# design.net
KiCad netlist of a schematic drawn in EasyEDA
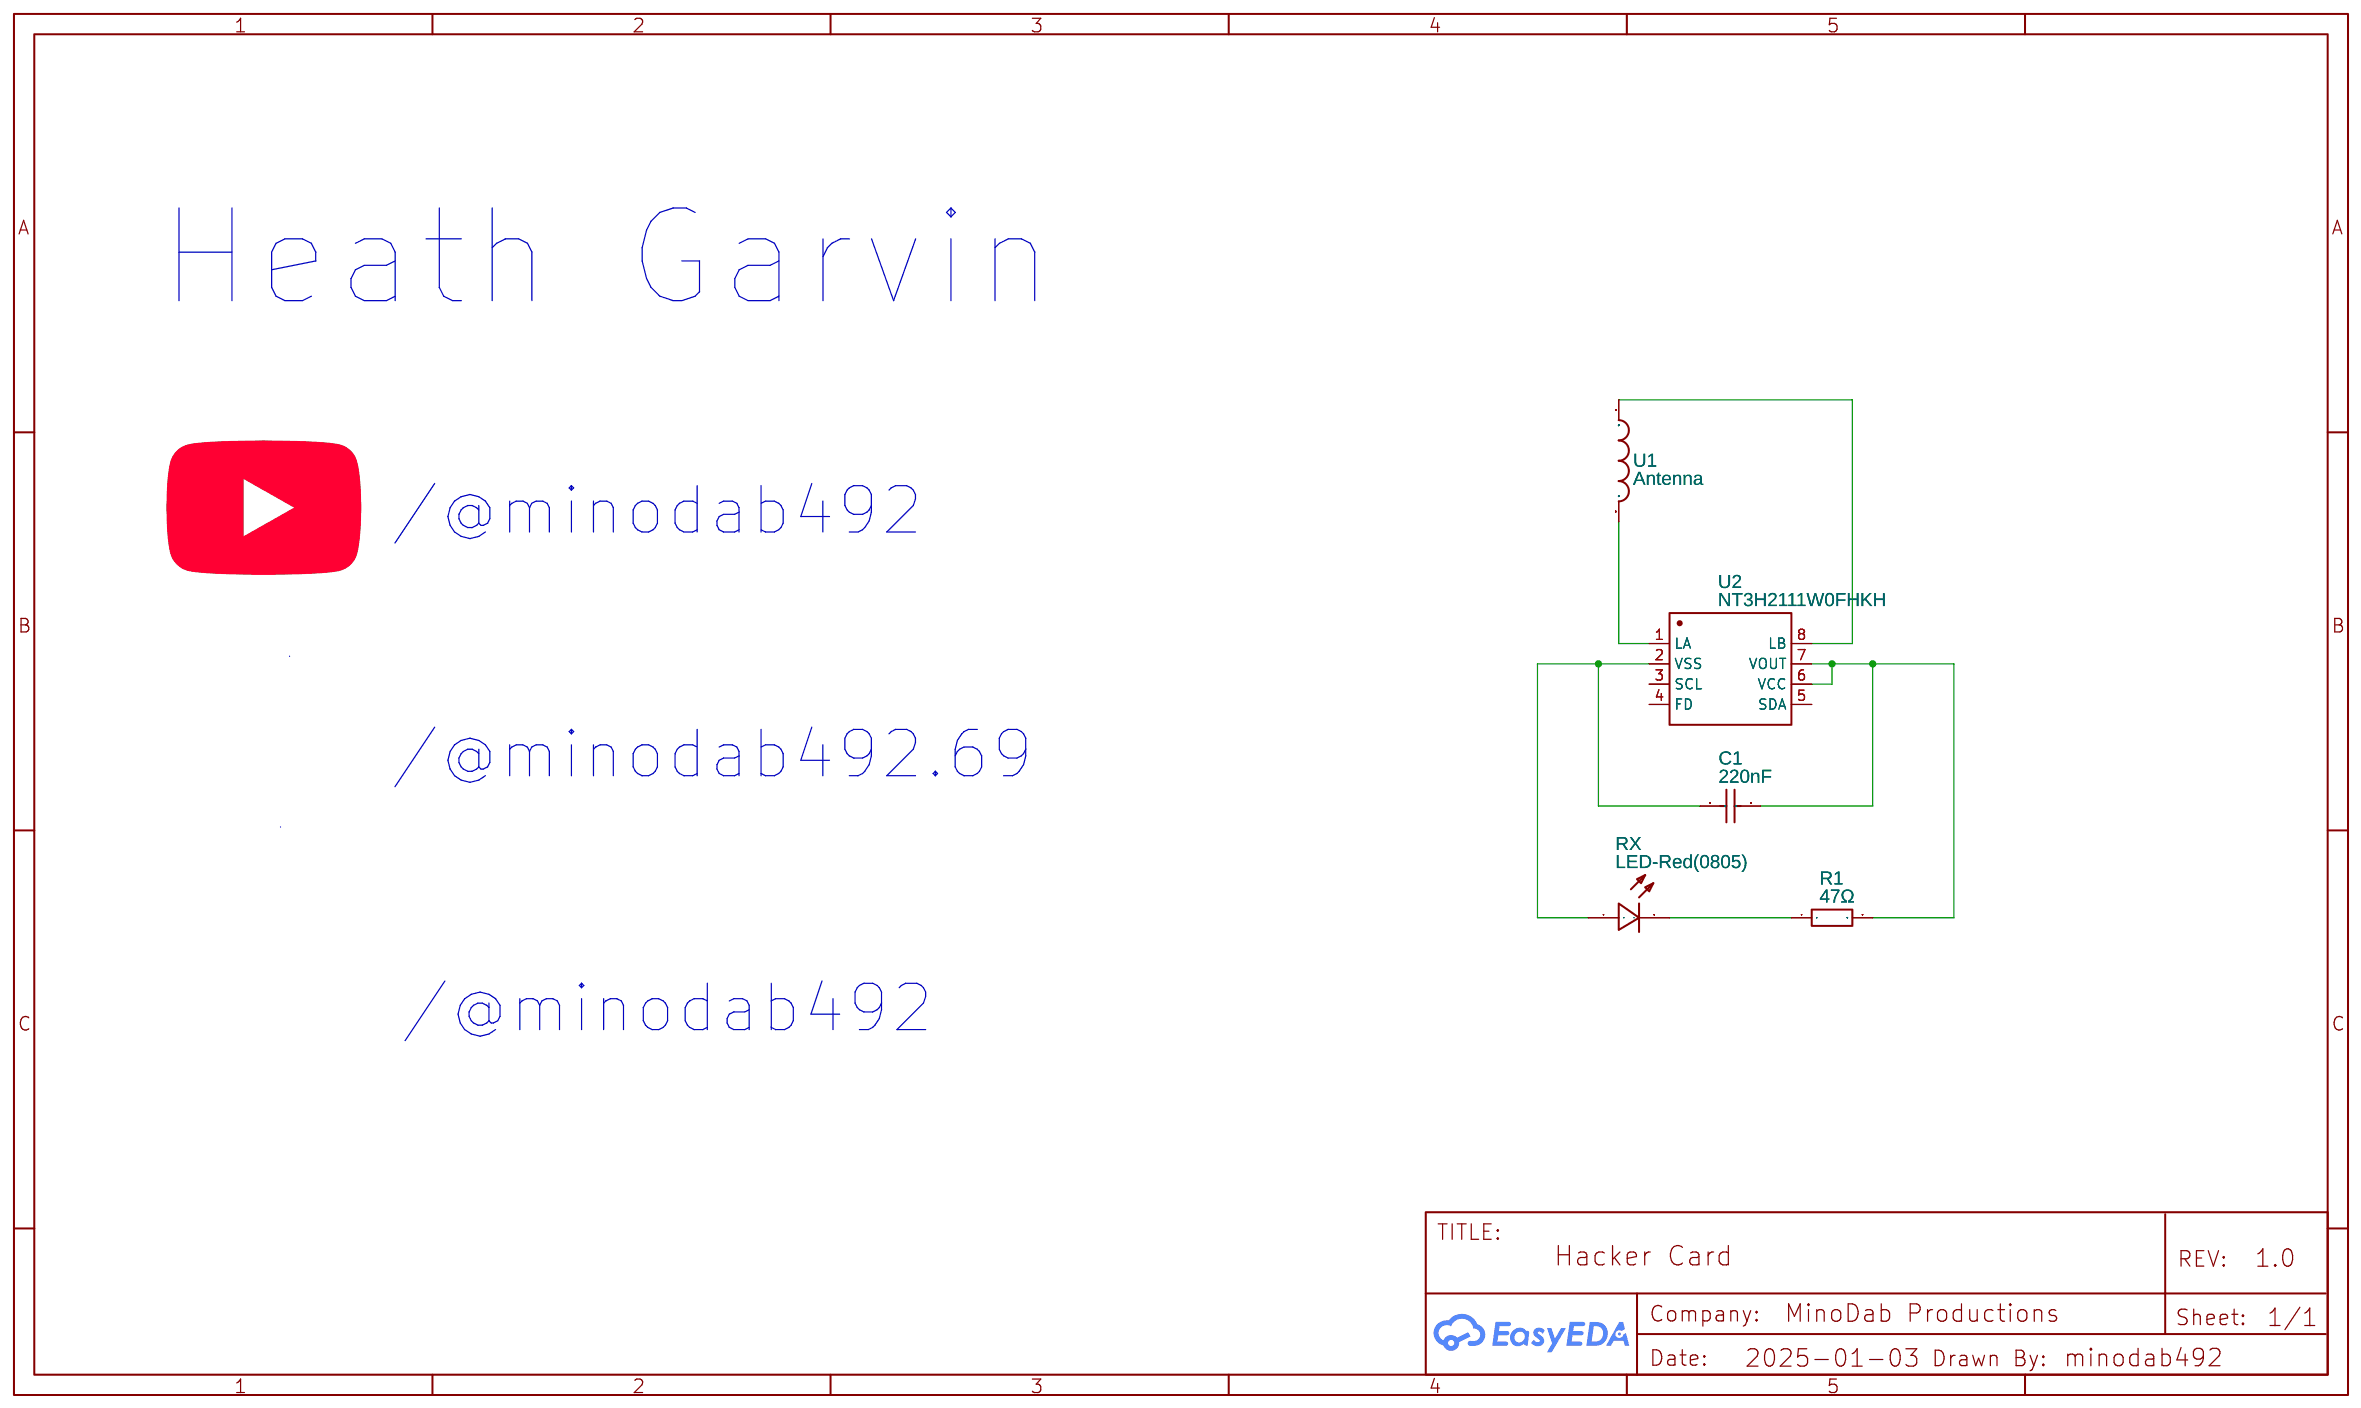
[diagram p0: schematic sheet]

(export (version "E")
  (design (tool "Eeschema 10.0.6"))
  (components
    (comp (ref "C1")
      (value "220nF")
      (fields
        (field (name "Manufacturer Part") "CL10B224KA8NNNC")
        (field (name "Manufacturer") "SAMSUNG(三星)")
      )
      (libsource (lib "") (part "CL10B224KA8NNNC"))
    )
    (comp (ref "R1")
      (value "47Ω")
      (fields
        (field (name "Manufacturer Part") "0603WAF470JT5E")
        (field (name "Manufacturer") "UNI-ROYAL(厚声)")
      )
      (libsource (lib "") (part "0603WAF470JT5E"))
    )
    (comp (ref "RX")
      (value "LED-Red(0805)")
      (fields
        (field (name "Manufacturer Part") "17-21SUYC/TR8")
        (field (name "Manufacturer") "Hubei KENTO Elec")
      )
      (libsource (lib "") (part "LED-Red(0805)"))
    )
    (comp (ref "U1") (value "Antenna") (libsource (lib "") (part "Antenna")))
    (comp (ref "U2")
      (value "NT3H2111W0FHKH")
      (fields (field (name "Manufacturer") "NXP(恩智浦)"))
      (libsource (lib "") (part "NT3H2111W0FHKH"))
    )
  )
  (nets
    (net (code "1") (name "Net-(RX-+)") (class "Default")
      (node (ref "C1") (pin "1") (pinfunction "1_1") (pintype "input"))
      (node (ref "RX") (pin "1") (pinfunction "+_1") (pintype "unspecified"))
      (node (ref "U2") (pin "2") (pinfunction "VSS_2") (pintype "unspecified"))
    )
    (net (code "2") (name "Net-(RX--)") (class "Default")
      (node (ref "R1") (pin "1") (pinfunction "1_1") (pintype "input"))
      (node (ref "RX") (pin "2") (pinfunction "-_2") (pintype "unspecified"))
    )
    (net (code "3") (name "Net-(U2-LA)") (class "Default")
      (node (ref "U1") (pin "P$1") (pinfunction "P$1_P$1") (pintype "unspecified"))
      (node (ref "U2") (pin "1") (pinfunction "LA_1") (pintype "unspecified"))
    )
    (net (code "4") (name "Net-(U2-LB)") (class "Default")
      (node (ref "U1") (pin "P$2") (pinfunction "P$2_P$2") (pintype "unspecified"))
      (node (ref "U2") (pin "8") (pinfunction "LB_8") (pintype "unspecified"))
    )
    (net (code "5") (name "Net-(U2-VCC)") (class "Default")
      (node (ref "C1") (pin "2") (pinfunction "2_2") (pintype "input"))
      (node (ref "R1") (pin "2") (pinfunction "2_2") (pintype "input"))
      (node (ref "U2") (pin "6") (pinfunction "VCC_6") (pintype "unspecified"))
      (node (ref "U2") (pin "7") (pinfunction "VOUT_7") (pintype "unspecified"))
    )
    (net (code "6") (name "unconnected-(U2-FD-Pad4)") (class "Default")
      (node (ref "U2") (pin "4") (pinfunction "FD_4") (pintype "unspecified"))
    )
    (net (code "7") (name "unconnected-(U2-SCL-Pad3)") (class "Default")
      (node (ref "U2") (pin "3") (pinfunction "SCL_3") (pintype "unspecified"))
    )
    (net (code "8") (name "unconnected-(U2-SDA-Pad5)") (class "Default")
      (node (ref "U2") (pin "5") (pinfunction "SDA_5") (pintype "unspecified"))
    )
  )
)
